# shematic.net
KiCad netlist of a schematic drawn in EAGLE
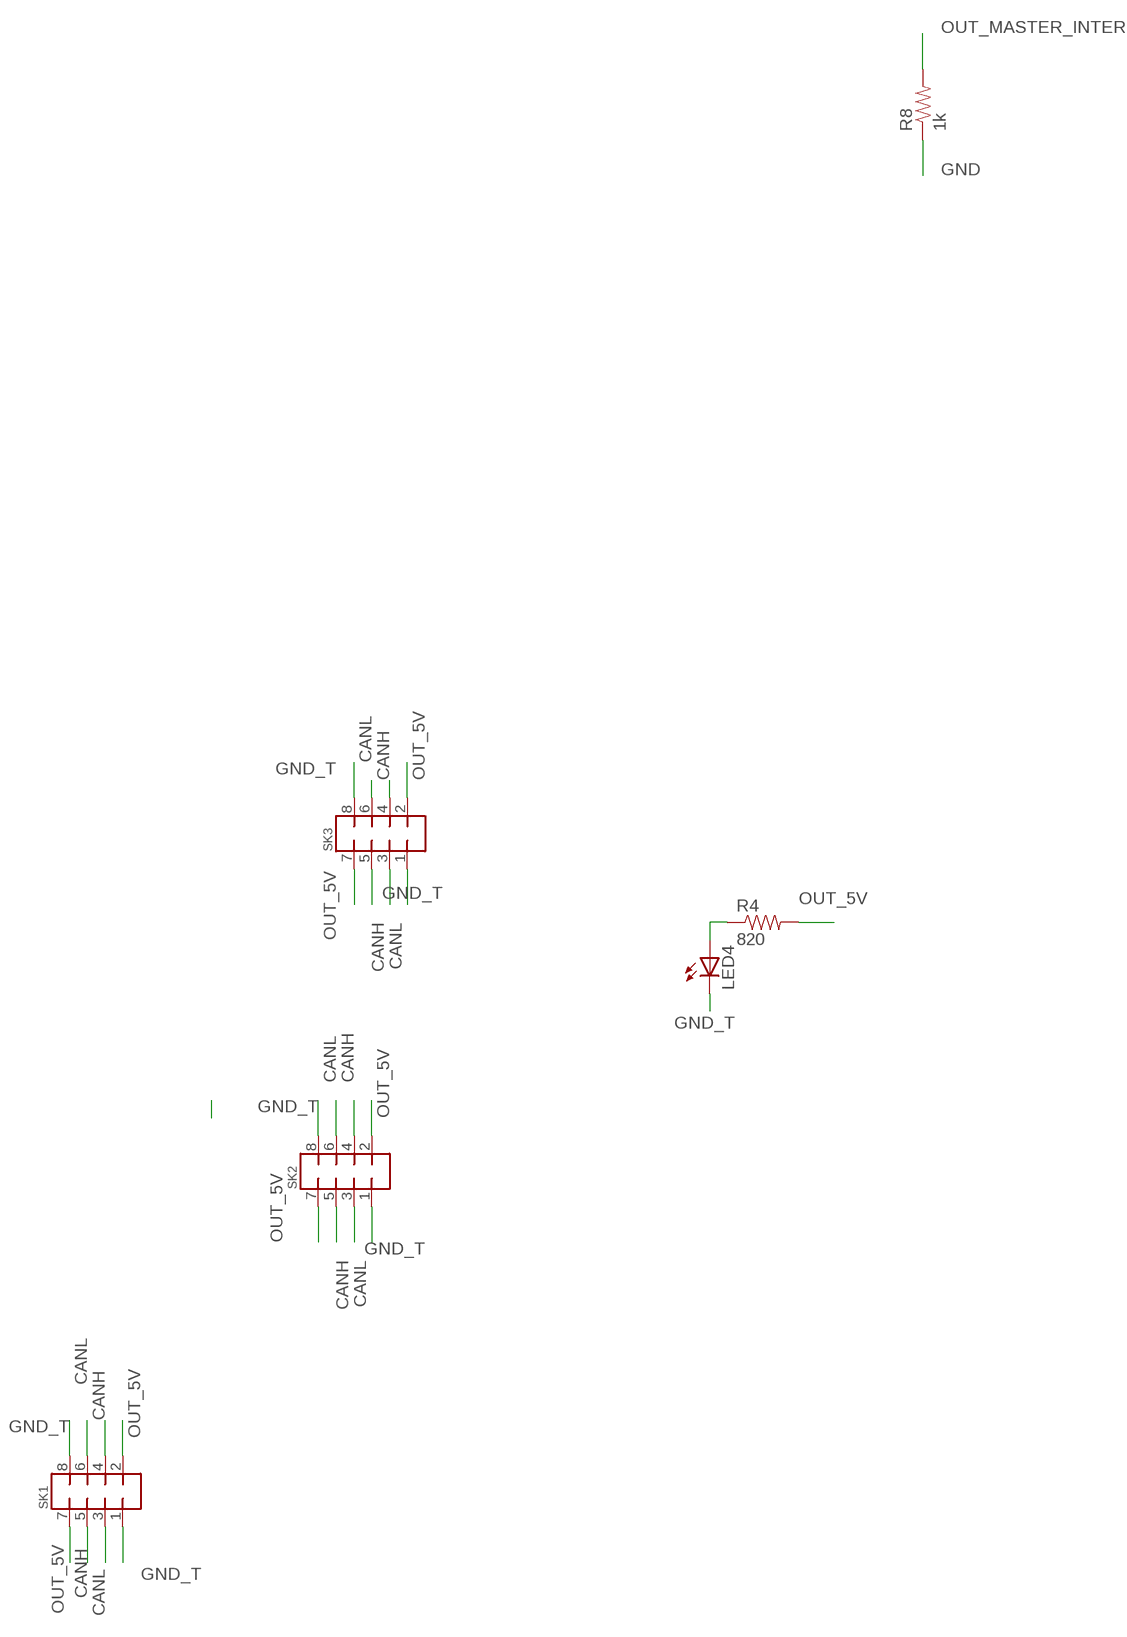
[diagram p0: schematic, sheet 1, part 1 of 2]
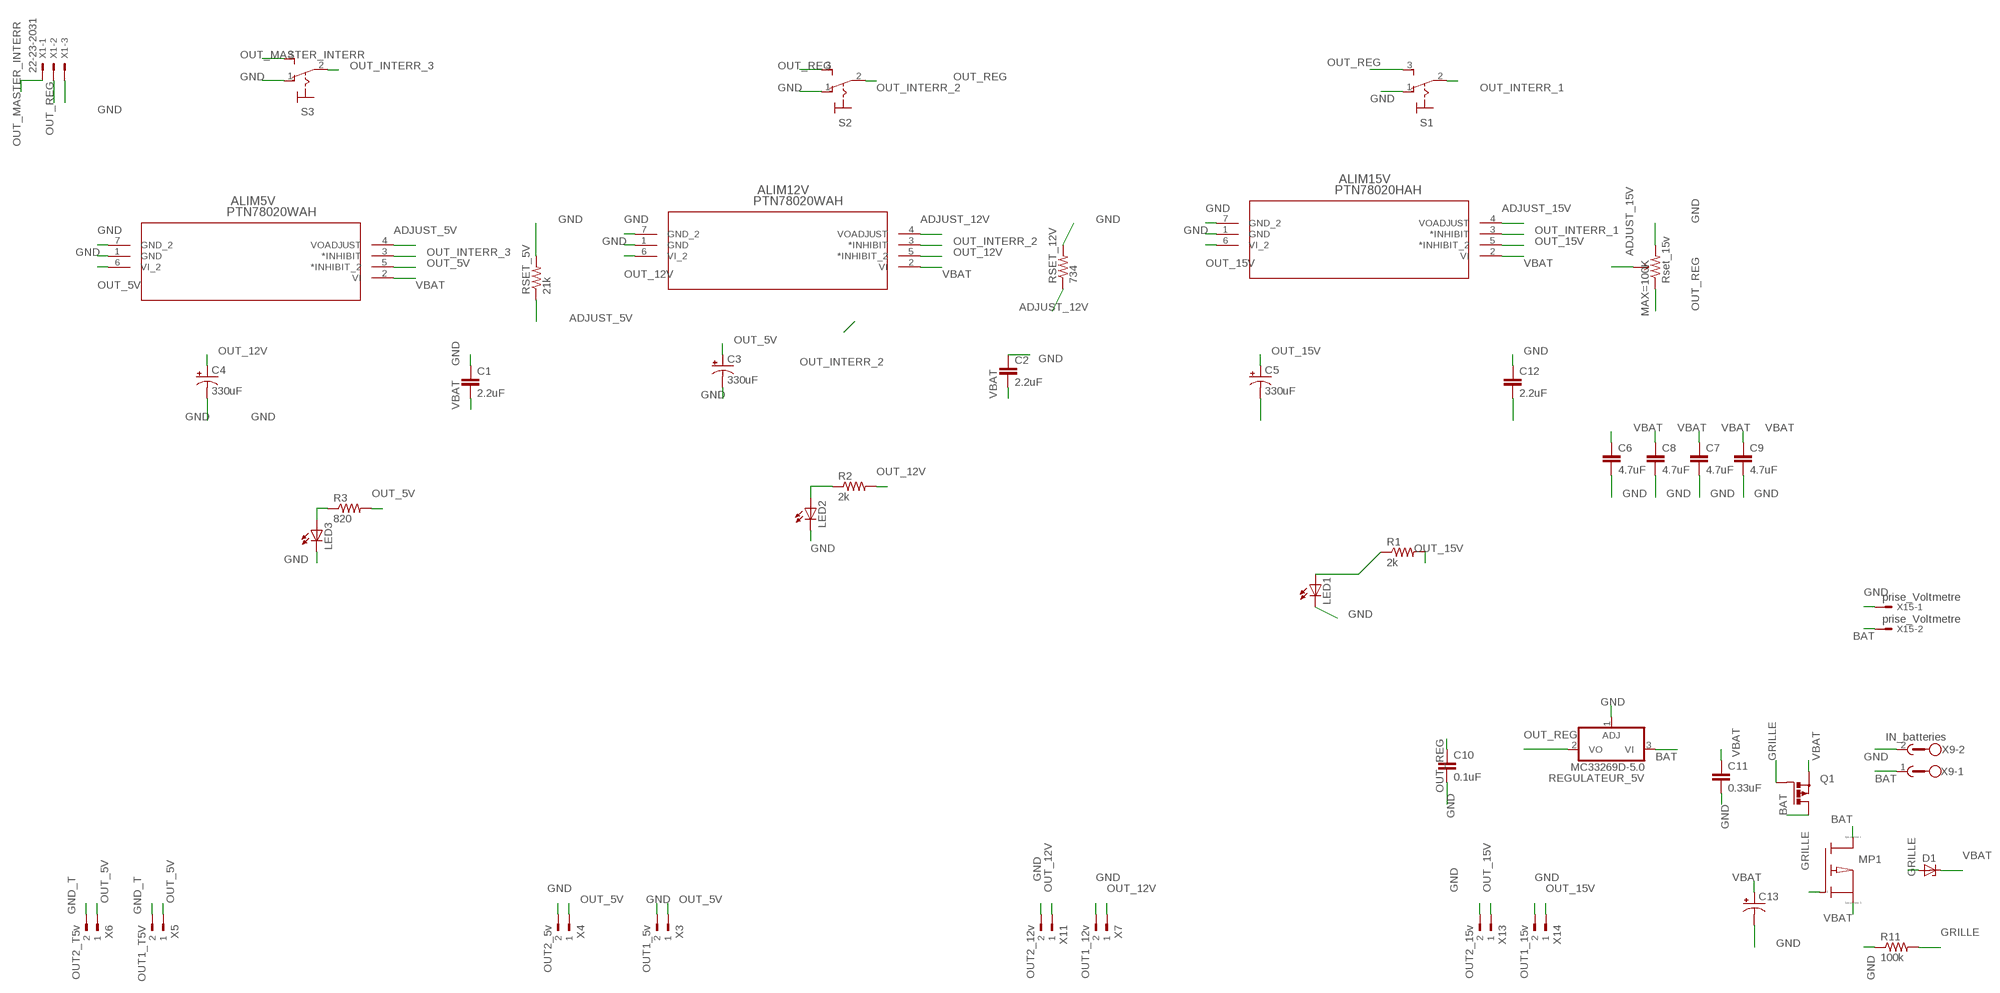
[diagram p1: schematic, sheet 1, part 2 of 2]

(export (version "E")
  (design (tool "Eeschema 10.0.6"))
  (components
    (comp (ref "ALIM5V")
      (value "PTN78020WAH")
      (footprint "eagle-import:EUK7")
      (libsource (lib "eagle-import") (part "PTN78020_"))
    )
    (comp (ref "ALIM12V")
      (value "PTN78020WAH")
      (footprint "eagle-import:EUK7")
      (libsource (lib "eagle-import") (part "PTN78020_"))
    )
    (comp (ref "ALIM15V")
      (value "PTN78020HAH")
      (footprint "eagle-import:EUK7")
      (libsource (lib "eagle-import") (part "PTN78020_"))
    )
    (comp (ref "C1")
      (value "2.2uF")
      (footprint "eagle-import:0805")
      (libsource (lib "eagle-import") (part "CAP0805"))
    )
    (comp (ref "C2")
      (value "2.2uF")
      (footprint "eagle-import:0805")
      (libsource (lib "eagle-import") (part "CAP0805"))
    )
    (comp (ref "C3")
      (value "330uF")
      (footprint "eagle-import:CPOL-RADIAL-100UF-25V")
      (libsource (lib "eagle-import") (part "CAP_POLPTH1"))
    )
    (comp (ref "C4")
      (value "330uF")
      (footprint "eagle-import:CPOL-RADIAL-100UF-25V")
      (libsource (lib "eagle-import") (part "CAP_POLPTH1"))
    )
    (comp (ref "C5")
      (value "330uF")
      (footprint "eagle-import:CPOL-RADIAL-100UF-25V")
      (libsource (lib "eagle-import") (part "CAP_POLPTH1"))
    )
    (comp (ref "C6")
      (value "4.7uF")
      (footprint "eagle-import:0805")
      (libsource (lib "eagle-import") (part "CAP0805"))
    )
    (comp (ref "C7")
      (value "4.7uF")
      (footprint "eagle-import:0805")
      (libsource (lib "eagle-import") (part "CAP0805"))
    )
    (comp (ref "C8")
      (value "4.7uF")
      (footprint "eagle-import:0805")
      (libsource (lib "eagle-import") (part "CAP0805"))
    )
    (comp (ref "C9")
      (value "4.7uF")
      (footprint "eagle-import:0805")
      (libsource (lib "eagle-import") (part "CAP0805"))
    )
    (comp (ref "C10")
      (value "0.1uF")
      (footprint "eagle-import:0805")
      (libsource (lib "eagle-import") (part "CAP0805"))
    )
    (comp (ref "C11")
      (value "0.33uF")
      (footprint "eagle-import:0805")
      (libsource (lib "eagle-import") (part "CAP0805"))
    )
    (comp (ref "C12")
      (value "2.2uF")
      (footprint "eagle-import:0805")
      (libsource (lib "eagle-import") (part "CAP0805"))
    )
    (comp (ref "C13")
      (value "CAP_POLPTH1")
      (footprint "eagle-import:CPOL-RADIAL-100UF-25V")
      (libsource (lib "eagle-import") (part "SparkFun-Passives_CAP_POLPTH1"))
    )
    (comp (ref "D1")
      (value "ZENER-DIODESOT23")
      (footprint "eagle-import:SOT23")
      (libsource (lib "eagle-import") (part "ZENER-DIODESOT23"))
    )
    (comp (ref "LED1")
      (value "LEDCHIP-LED0805")
      (footprint "eagle-import:CHIP-LED0805")
      (libsource (lib "eagle-import") (part "LEDCHIP-LED0805"))
    )
    (comp (ref "LED2")
      (value "LEDCHIP-LED0805")
      (footprint "eagle-import:CHIP-LED0805")
      (libsource (lib "eagle-import") (part "LEDCHIP-LED0805"))
    )
    (comp (ref "LED3")
      (value "LEDCHIP-LED0805")
      (footprint "eagle-import:CHIP-LED0805")
      (libsource (lib "eagle-import") (part "LEDCHIP-LED0805"))
    )
    (comp (ref "LED4")
      (value "LEDCHIP-LED0805")
      (footprint "eagle-import:CHIP-LED0805")
      (libsource (lib "eagle-import") (part "LEDCHIP-LED0805"))
    )
    (comp (ref "MAX=100K")
      (value "Rset_15v")
      (footprint "eagle-import:3386U")
      (libsource (lib "eagle-import") (part "TRIMPOT-PTH-KNOB"))
    )
    (comp (ref "MP1")
      (value "PMOS")
      (footprint "eagle-import:SOT23")
      (libsource (lib "eagle-import") (part "PMOS"))
    )
    (comp (ref "Q1")
      (value "PMOSFET_PTO220BH")
      (footprint "eagle-import:TO220BH")
      (libsource (lib "eagle-import") (part "PMOSFET_PTO220BH"))
    )
    (comp (ref "R1")
      (value "2k")
      (footprint "eagle-import:0805")
      (libsource (lib "eagle-import") (part "SparkFun-Resistors_RESISTOR0805-RES"))
    )
    (comp (ref "R2")
      (value "2k")
      (footprint "eagle-import:0805")
      (libsource (lib "eagle-import") (part "SparkFun-Resistors_RESISTOR0805-RES"))
    )
    (comp (ref "R3")
      (value "820")
      (footprint "eagle-import:0805")
      (libsource (lib "eagle-import") (part "SparkFun-Resistors_RESISTOR0805-RES"))
    )
    (comp (ref "R4")
      (value "820")
      (footprint "eagle-import:0805")
      (libsource (lib "eagle-import") (part "SparkFun-Resistors_RESISTOR0805-RES"))
    )
    (comp (ref "R8")
      (value "1k")
      (footprint "eagle-import:0805")
      (libsource (lib "eagle-import") (part "SparkFun-Resistors_RESISTOR0805-RES"))
    )
    (comp (ref "R11")
      (value "100k")
      (footprint "eagle-import:0805")
      (libsource (lib "eagle-import") (part "RESISTOR0805-RES"))
    )
    (comp (ref "REGULATEUR_5V")
      (value "MC33269D-5.0")
      (footprint "eagle-import:DPACK")
      (libsource (lib "eagle-import") (part "MC33269?D-5.0"))
    )
    (comp (ref "RSET_5V")
      (value "21k")
      (footprint "eagle-import:0805")
      (libsource (lib "eagle-import") (part "RESISTOR0805-RES"))
    )
    (comp (ref "RSET_12V")
      (value "734")
      (footprint "eagle-import:0805")
      (libsource (lib "eagle-import") (part "RESISTOR0805-RES"))
    )
    (comp (ref "S1")
      (value "M9040P")
      (footprint "eagle-import:M9040P")
      (libsource (lib "eagle-import") (part "M9040P"))
    )
    (comp (ref "S2")
      (value "M9040P")
      (footprint "eagle-import:M9040P")
      (libsource (lib "eagle-import") (part "M9040P"))
    )
    (comp (ref "S3")
      (value "M9040P")
      (footprint "eagle-import:M9040P")
      (libsource (lib "eagle-import") (part "M9040P"))
    )
    (comp (ref "SK1")
      (value "MMATCH-8-PTH")
      (footprint "eagle-import:AMP-215079-8")
      (libsource (lib "eagle-import") (part "MMATCH-8-PTH"))
    )
    (comp (ref "SK2")
      (value "MMATCH-8-PTH")
      (footprint "eagle-import:AMP-215079-8")
      (libsource (lib "eagle-import") (part "MMATCH-8-PTH"))
    )
    (comp (ref "SK3")
      (value "MMATCH-8-PTH")
      (footprint "eagle-import:AMP-215079-8")
      (libsource (lib "eagle-import") (part "MMATCH-8-PTH"))
    )
    (comp (ref "X1")
      (value "22-23-2031")
      (footprint "eagle-import:22-23-2031")
      (fields (field (name "MF") "MOLEX"))
      (libsource (lib "eagle-import") (part "22-23-2031"))
    )
    (comp (ref "X3")
      (value "OUT1_5v")
      (footprint "eagle-import:90-2")
      (libsource (lib "eagle-import") (part "90-2"))
    )
    (comp (ref "X4")
      (value "OUT2_5v")
      (footprint "eagle-import:90-2")
      (libsource (lib "eagle-import") (part "90-2"))
    )
    (comp (ref "X5")
      (value "OUT1_T5V")
      (footprint "eagle-import:90-2")
      (libsource (lib "eagle-import") (part "90-2"))
    )
    (comp (ref "X6")
      (value "OUT2_T5v")
      (footprint "eagle-import:90-2")
      (libsource (lib "eagle-import") (part "90-2"))
    )
    (comp (ref "X7")
      (value "OUT1_12v")
      (footprint "eagle-import:90-2")
      (libsource (lib "eagle-import") (part "90-2"))
    )
    (comp (ref "X9")
      (value "IN_batteries")
      (footprint "eagle-import:GMSTBA2")
      (fields (field (name "MF") "FARNELL") (field (name "MPN") "1757242"))
      (libsource (lib "eagle-import") (part "GMSTBA2"))
    )
    (comp (ref "X11")
      (value "OUT2_12v")
      (footprint "eagle-import:90-2")
      (libsource (lib "eagle-import") (part "90-2"))
    )
    (comp (ref "X13")
      (value "OUT2_15v")
      (footprint "eagle-import:90-2")
      (libsource (lib "eagle-import") (part "90-2"))
    )
    (comp (ref "X14")
      (value "OUT1_15v")
      (footprint "eagle-import:90-2")
      (libsource (lib "eagle-import") (part "90-2"))
    )
    (comp (ref "X15")
      (value "prise_Voltmetre")
      (footprint "eagle-import:KK-156-2")
      (libsource (lib "eagle-import") (part "KK-156-2"))
    )
  )
  (nets
    (net (code "1") (name "/ADJUST_5V") (class "Default")
      (node (ref "ALIM5V") (pin "4") (pinfunction "VOADJUST_4") (pintype "passive"))
      (node (ref "RSET_5V") (pin "1") (pinfunction "1_1") (pintype "passive"))
    )
    (net (code "2") (name "/ADJUST_12V") (class "Default")
      (node (ref "ALIM12V") (pin "4") (pinfunction "VOADJUST_4") (pintype "passive"))
      (node (ref "RSET_12V") (pin "1") (pinfunction "1_1") (pintype "passive"))
    )
    (net (code "3") (name "/ADJUST_15V") (class "Default")
      (node (ref "ALIM15V") (pin "4") (pinfunction "VOADJUST_4") (pintype "passive"))
      (node (ref "MAX=100K") (pin "2") (pinfunction "WIPER_2") (pintype "passive"))
    )
    (net (code "4") (name "/BAT") (class "Default")
      (node (ref "MP1") (pin "3") (pinfunction "D_3") (pintype "passive"))
      (node (ref "Q1") (pin "D") (pinfunction "D_D") (pintype "passive"))
      (node (ref "REGULATEUR_5V") (pin "3") (pinfunction "VI_3") (pintype "input"))
      (node (ref "X15") (pin "2") (pinfunction "S_2") (pintype "passive"))
      (node (ref "X9") (pin "1") (pinfunction "1_1") (pintype "passive"))
    )
    (net (code "5") (name "/CANH") (class "Default")
      (node (ref "SK1") (pin "4") (pinfunction "4_4") (pintype "bidirectional"))
      (node (ref "SK1") (pin "5") (pinfunction "5_5") (pintype "bidirectional"))
      (node (ref "SK2") (pin "4") (pinfunction "4_4") (pintype "bidirectional"))
      (node (ref "SK2") (pin "5") (pinfunction "5_5") (pintype "bidirectional"))
      (node (ref "SK3") (pin "4") (pinfunction "4_4") (pintype "bidirectional"))
      (node (ref "SK3") (pin "5") (pinfunction "5_5") (pintype "bidirectional"))
    )
    (net (code "6") (name "/CANL") (class "Default")
      (node (ref "SK1") (pin "3") (pinfunction "3_3") (pintype "bidirectional"))
      (node (ref "SK1") (pin "6") (pinfunction "6_6") (pintype "bidirectional"))
      (node (ref "SK2") (pin "3") (pinfunction "3_3") (pintype "bidirectional"))
      (node (ref "SK2") (pin "6") (pinfunction "6_6") (pintype "bidirectional"))
      (node (ref "SK3") (pin "3") (pinfunction "3_3") (pintype "bidirectional"))
      (node (ref "SK3") (pin "6") (pinfunction "6_6") (pintype "bidirectional"))
    )
    (net (code "7") (name "/GND") (class "Default")
      (node (ref "ALIM12V") (pin "1") (pinfunction "GND_1") (pintype "passive"))
      (node (ref "ALIM12V") (pin "7") (pinfunction "GND_2_7") (pintype "passive"))
      (node (ref "ALIM15V") (pin "1") (pinfunction "GND_1") (pintype "passive"))
      (node (ref "ALIM15V") (pin "7") (pinfunction "GND_2_7") (pintype "passive"))
      (node (ref "ALIM5V") (pin "1") (pinfunction "GND_1") (pintype "passive"))
      (node (ref "ALIM5V") (pin "7") (pinfunction "GND_2_7") (pintype "passive"))
      (node (ref "C1") (pin "1") (pinfunction "1_1") (pintype "passive"))
      (node (ref "C10") (pin "2") (pinfunction "2_2") (pintype "passive"))
      (node (ref "C11") (pin "2") (pinfunction "2_2") (pintype "passive"))
      (node (ref "C12") (pin "1") (pinfunction "1_1") (pintype "passive"))
      (node (ref "C13") (pin "2") (pinfunction "-_2") (pintype "passive"))
      (node (ref "C2") (pin "1") (pinfunction "1_1") (pintype "passive"))
      (node (ref "C3") (pin "2") (pinfunction "-_2") (pintype "passive"))
      (node (ref "C4") (pin "2") (pinfunction "-_2") (pintype "passive"))
      (node (ref "C5") (pin "2") (pinfunction "-_2") (pintype "passive"))
      (node (ref "C6") (pin "2") (pinfunction "2_2") (pintype "passive"))
      (node (ref "C7") (pin "2") (pinfunction "2_2") (pintype "passive"))
      (node (ref "C8") (pin "2") (pinfunction "2_2") (pintype "passive"))
      (node (ref "C9") (pin "2") (pinfunction "2_2") (pintype "passive"))
      (node (ref "LED1") (pin "C") (pinfunction "C_C") (pintype "passive"))
      (node (ref "LED2") (pin "C") (pinfunction "C_C") (pintype "passive"))
      (node (ref "LED3") (pin "C") (pinfunction "C_C") (pintype "passive"))
      (node (ref "MAX=100K") (pin "3") (pinfunction "CW_3") (pintype "passive"))
      (node (ref "R11") (pin "1") (pinfunction "1_1") (pintype "passive"))
      (node (ref "R8") (pin "1") (pinfunction "1_1") (pintype "passive"))
      (node (ref "REGULATEUR_5V") (pin "1") (pinfunction "ADJ_1") (pintype "input"))
      (node (ref "RSET_12V") (pin "2") (pinfunction "2_2") (pintype "passive"))
      (node (ref "RSET_5V") (pin "2") (pinfunction "2_2") (pintype "passive"))
      (node (ref "S1") (pin "1") (pinfunction "O_1") (pintype "passive"))
      (node (ref "S2") (pin "1") (pinfunction "O_1") (pintype "passive"))
      (node (ref "S3") (pin "1") (pinfunction "O_1") (pintype "passive"))
      (node (ref "X1") (pin "3") (pinfunction "S_3") (pintype "passive"))
      (node (ref "X11") (pin "2") (pinfunction "2_2") (pintype "passive"))
      (node (ref "X13") (pin "2") (pinfunction "2_2") (pintype "passive"))
      (node (ref "X14") (pin "2") (pinfunction "2_2") (pintype "passive"))
      (node (ref "X15") (pin "1") (pinfunction "S_1") (pintype "passive"))
      (node (ref "X3") (pin "2") (pinfunction "2_2") (pintype "passive"))
      (node (ref "X4") (pin "2") (pinfunction "2_2") (pintype "passive"))
      (node (ref "X7") (pin "2") (pinfunction "2_2") (pintype "passive"))
      (node (ref "X9") (pin "2") (pinfunction "1_2") (pintype "passive"))
    )
    (net (code "8") (name "/GND_T") (class "Default")
      (node (ref "LED4") (pin "C") (pinfunction "C_C") (pintype "passive"))
      (node (ref "SK1") (pin "1") (pinfunction "1_1") (pintype "bidirectional"))
      (node (ref "SK1") (pin "8") (pinfunction "8_8") (pintype "bidirectional"))
      (node (ref "SK2") (pin "1") (pinfunction "1_1") (pintype "bidirectional"))
      (node (ref "SK2") (pin "8") (pinfunction "8_8") (pintype "bidirectional"))
      (node (ref "SK3") (pin "1") (pinfunction "1_1") (pintype "bidirectional"))
      (node (ref "SK3") (pin "8") (pinfunction "8_8") (pintype "bidirectional"))
      (node (ref "X5") (pin "2") (pinfunction "2_2") (pintype "passive"))
      (node (ref "X6") (pin "2") (pinfunction "2_2") (pintype "passive"))
    )
    (net (code "9") (name "/GRILLE") (class "Default")
      (node (ref "D1") (pin "1") (pinfunction "A_1") (pintype "passive"))
      (node (ref "MP1") (pin "1") (pinfunction "G_1") (pintype "passive"))
      (node (ref "Q1") (pin "G") (pinfunction "G_G") (pintype "passive"))
      (node (ref "R11") (pin "2") (pinfunction "2_2") (pintype "passive"))
    )
    (net (code "10") (name "/OUT_5V") (class "Default")
      (node (ref "ALIM5V") (pin "5") (pinfunction "*INHIBIT_2_5") (pintype "passive"))
      (node (ref "ALIM5V") (pin "6") (pinfunction "VI_2_6") (pintype "passive"))
      (node (ref "C3") (pin "1") (pinfunction "+_1") (pintype "passive"))
      (node (ref "R3") (pin "2") (pinfunction "2_2") (pintype "passive"))
      (node (ref "R4") (pin "2") (pinfunction "2_2") (pintype "passive"))
      (node (ref "SK1") (pin "2") (pinfunction "2_2") (pintype "bidirectional"))
      (node (ref "SK1") (pin "7") (pinfunction "7_7") (pintype "bidirectional"))
      (node (ref "SK2") (pin "2") (pinfunction "2_2") (pintype "bidirectional"))
      (node (ref "SK2") (pin "7") (pinfunction "7_7") (pintype "bidirectional"))
      (node (ref "SK3") (pin "2") (pinfunction "2_2") (pintype "bidirectional"))
      (node (ref "SK3") (pin "7") (pinfunction "7_7") (pintype "bidirectional"))
      (node (ref "X3") (pin "1") (pinfunction "1_1") (pintype "passive"))
      (node (ref "X4") (pin "1") (pinfunction "1_1") (pintype "passive"))
      (node (ref "X5") (pin "1") (pinfunction "1_1") (pintype "passive"))
      (node (ref "X6") (pin "1") (pinfunction "1_1") (pintype "passive"))
    )
    (net (code "11") (name "/OUT_12V") (class "Default")
      (node (ref "ALIM12V") (pin "5") (pinfunction "*INHIBIT_2_5") (pintype "passive"))
      (node (ref "ALIM12V") (pin "6") (pinfunction "VI_2_6") (pintype "passive"))
      (node (ref "C4") (pin "1") (pinfunction "+_1") (pintype "passive"))
      (node (ref "R2") (pin "2") (pinfunction "2_2") (pintype "passive"))
      (node (ref "X11") (pin "1") (pinfunction "1_1") (pintype "passive"))
      (node (ref "X7") (pin "1") (pinfunction "1_1") (pintype "passive"))
    )
    (net (code "12") (name "/OUT_15V") (class "Default")
      (node (ref "ALIM15V") (pin "5") (pinfunction "*INHIBIT_2_5") (pintype "passive"))
      (node (ref "ALIM15V") (pin "6") (pinfunction "VI_2_6") (pintype "passive"))
      (node (ref "C5") (pin "1") (pinfunction "+_1") (pintype "passive"))
      (node (ref "R1") (pin "2") (pinfunction "2_2") (pintype "passive"))
      (node (ref "X13") (pin "1") (pinfunction "1_1") (pintype "passive"))
      (node (ref "X14") (pin "1") (pinfunction "1_1") (pintype "passive"))
    )
    (net (code "13") (name "/OUT_INTERR_1") (class "Default")
      (node (ref "ALIM15V") (pin "3") (pinfunction "*INHIBIT_3") (pintype "passive"))
      (node (ref "S1") (pin "2") (pinfunction "P_2") (pintype "passive"))
    )
    (net (code "14") (name "/OUT_INTERR_2") (class "Default")
      (node (ref "ALIM12V") (pin "3") (pinfunction "*INHIBIT_3") (pintype "passive"))
      (node (ref "S2") (pin "2") (pinfunction "P_2") (pintype "passive"))
    )
    (net (code "15") (name "/OUT_INTERR_3") (class "Default")
      (node (ref "ALIM5V") (pin "3") (pinfunction "*INHIBIT_3") (pintype "passive"))
      (node (ref "S3") (pin "2") (pinfunction "P_2") (pintype "passive"))
    )
    (net (code "16") (name "/OUT_MASTER_INTERR") (class "Default")
      (node (ref "R8") (pin "2") (pinfunction "2_2") (pintype "passive"))
      (node (ref "S3") (pin "3") (pinfunction "S_3") (pintype "passive"))
      (node (ref "X1") (pin "1") (pinfunction "S_1") (pintype "passive"))
    )
    (net (code "17") (name "/OUT_REG") (class "Default")
      (node (ref "C10") (pin "1") (pinfunction "1_1") (pintype "passive"))
      (node (ref "MAX=100K") (pin "1") (pinfunction "CCW_1") (pintype "passive"))
      (node (ref "REGULATEUR_5V") (pin "2") (pinfunction "VO_2") (pintype "passive"))
      (node (ref "S1") (pin "3") (pinfunction "S_3") (pintype "passive"))
      (node (ref "S2") (pin "3") (pinfunction "S_3") (pintype "passive"))
      (node (ref "X1") (pin "2") (pinfunction "S_2") (pintype "passive"))
    )
    (net (code "18") (name "/VBAT") (class "Default")
      (node (ref "ALIM12V") (pin "2") (pinfunction "VI_2") (pintype "passive"))
      (node (ref "ALIM15V") (pin "2") (pinfunction "VI_2") (pintype "passive"))
      (node (ref "ALIM5V") (pin "2") (pinfunction "VI_2") (pintype "passive"))
      (node (ref "C1") (pin "2") (pinfunction "2_2") (pintype "passive"))
      (node (ref "C11") (pin "1") (pinfunction "1_1") (pintype "passive"))
      (node (ref "C12") (pin "2") (pinfunction "2_2") (pintype "passive"))
      (node (ref "C13") (pin "1") (pinfunction "+_1") (pintype "passive"))
      (node (ref "C2") (pin "2") (pinfunction "2_2") (pintype "passive"))
      (node (ref "C6") (pin "1") (pinfunction "1_1") (pintype "passive"))
      (node (ref "C7") (pin "1") (pinfunction "1_1") (pintype "passive"))
      (node (ref "C8") (pin "1") (pinfunction "1_1") (pintype "passive"))
      (node (ref "C9") (pin "1") (pinfunction "1_1") (pintype "passive"))
      (node (ref "D1") (pin "3") (pinfunction "C_3") (pintype "passive"))
      (node (ref "MP1") (pin "2") (pinfunction "S_2") (pintype "passive"))
      (node (ref "Q1") (pin "S") (pinfunction "S_S") (pintype "passive"))
    )
    (net (code "19") (name "Net-(LED1-PadA)") (class "Default")
      (node (ref "LED1") (pin "A") (pinfunction "A_A") (pintype "passive"))
      (node (ref "R1") (pin "1") (pinfunction "1_1") (pintype "passive"))
    )
    (net (code "20") (name "Net-(LED2-PadA)") (class "Default")
      (node (ref "LED2") (pin "A") (pinfunction "A_A") (pintype "passive"))
      (node (ref "R2") (pin "1") (pinfunction "1_1") (pintype "passive"))
    )
    (net (code "21") (name "Net-(LED3-PadA)") (class "Default")
      (node (ref "LED3") (pin "A") (pinfunction "A_A") (pintype "passive"))
      (node (ref "R3") (pin "1") (pinfunction "1_1") (pintype "passive"))
    )
    (net (code "22") (name "Net-(LED4-PadA)") (class "Default")
      (node (ref "LED4") (pin "A") (pinfunction "A_A") (pintype "passive"))
      (node (ref "R4") (pin "1") (pinfunction "1_1") (pintype "passive"))
    )
  )
)
